# plc_esp32.net
KiCad netlist of a schematic drawn in EAGLE
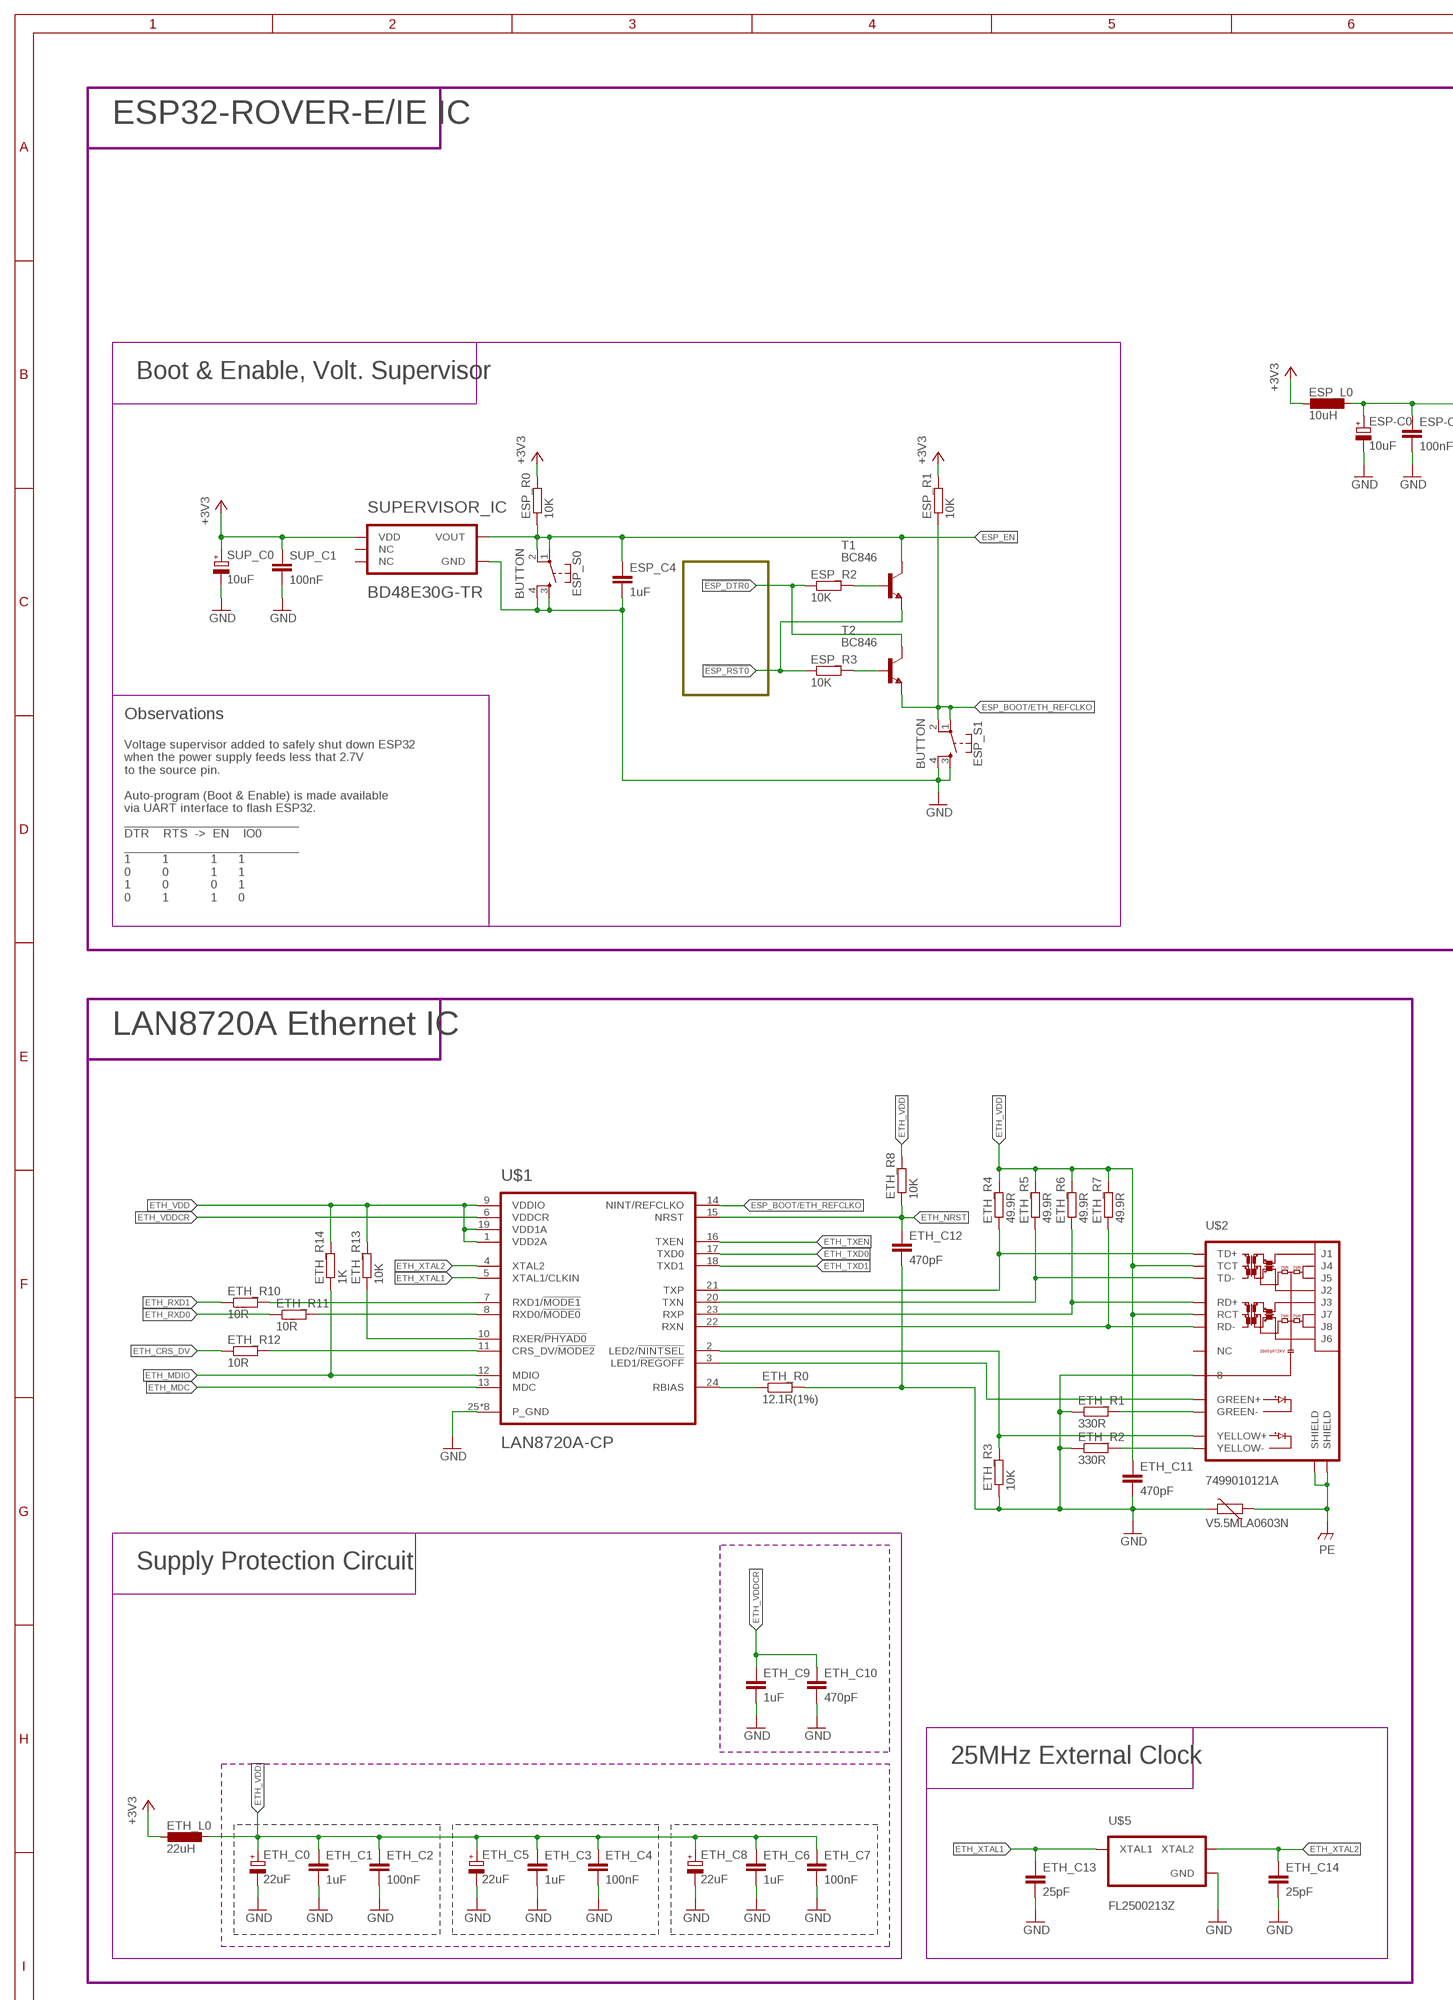
[diagram p0: schematic, sheet 1, part 1 of 2]
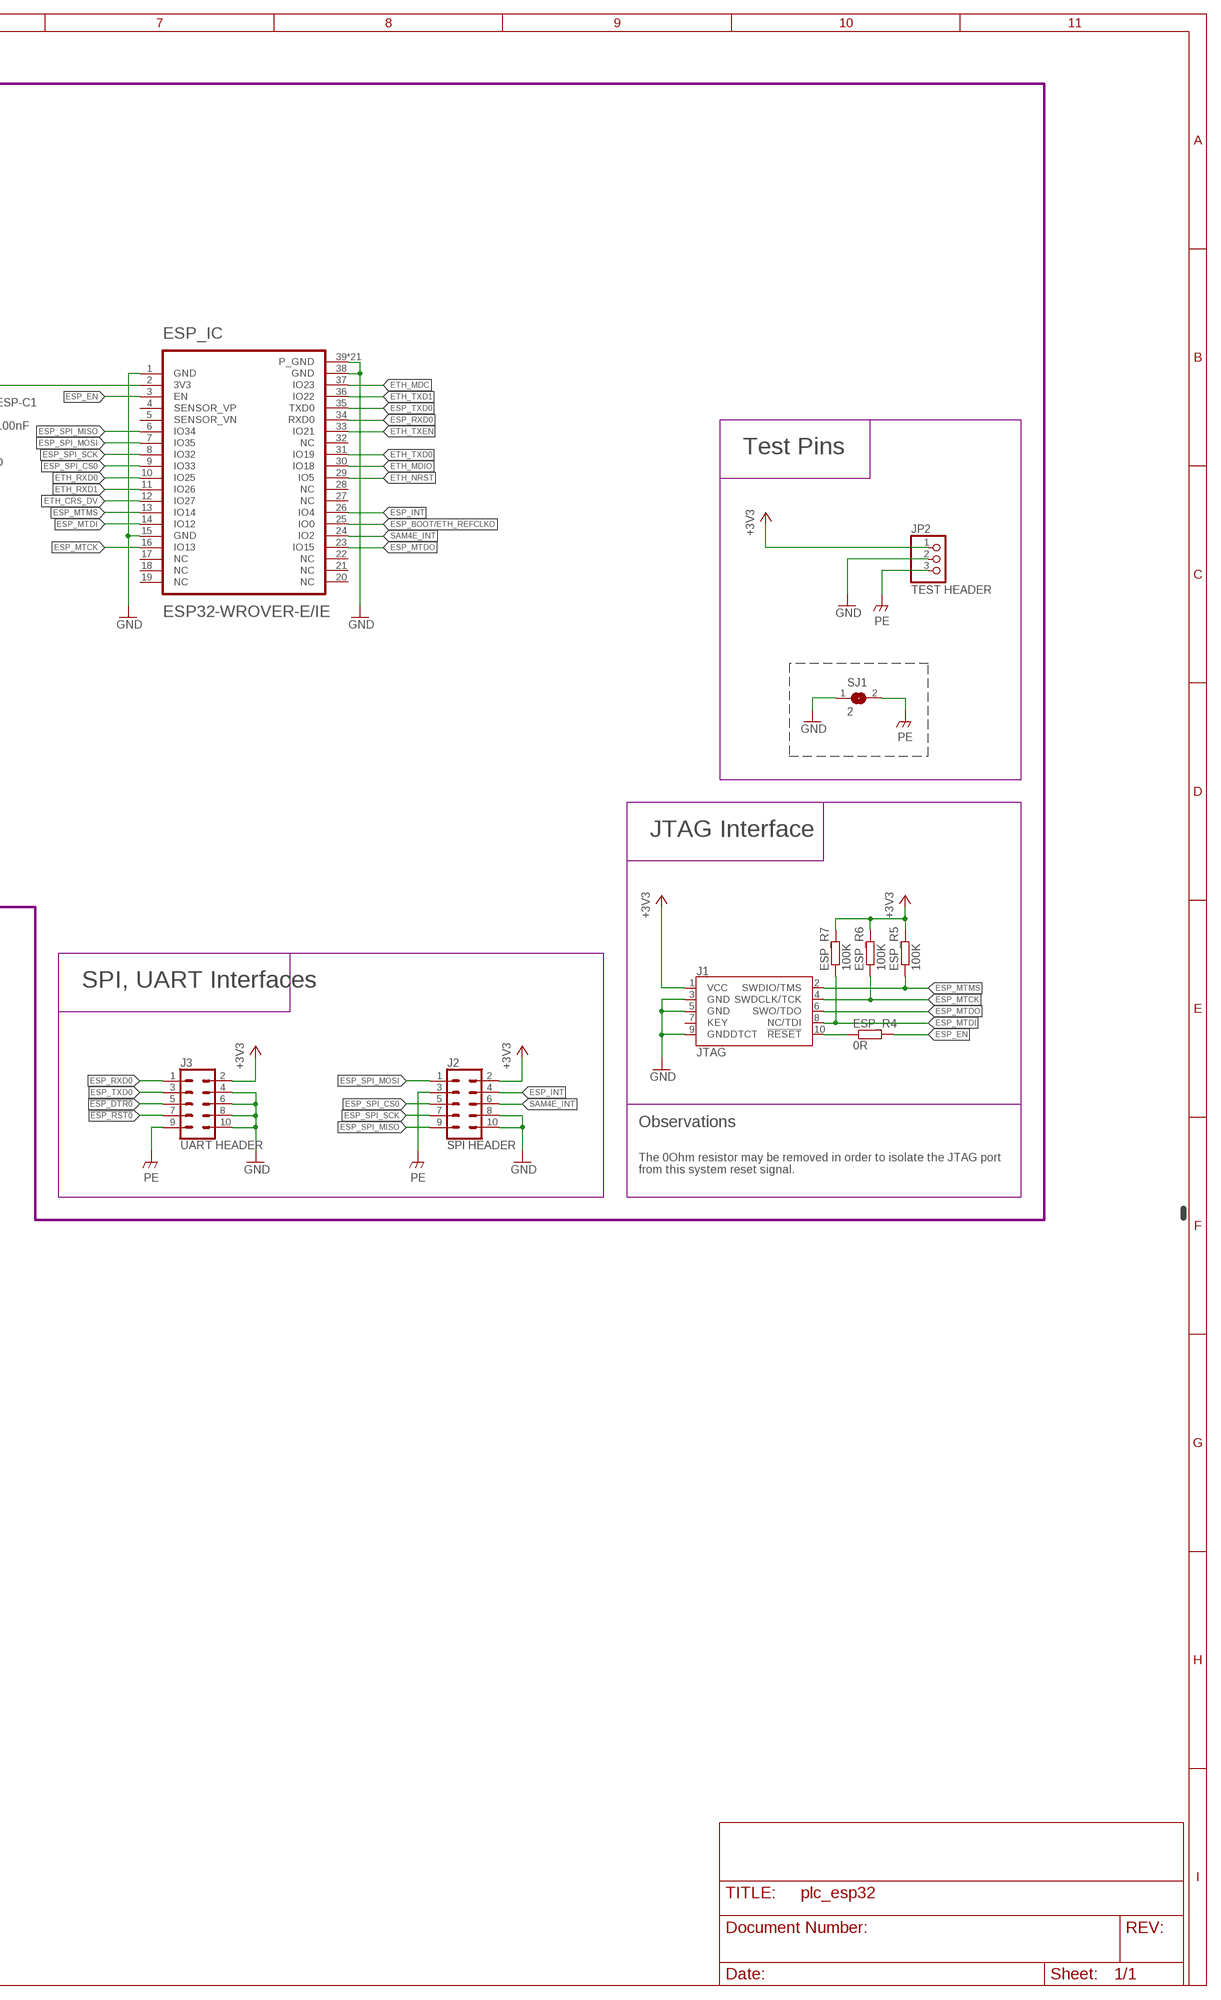
[diagram p1: schematic, sheet 1, part 2 of 2]

(export (version "E")
  (design (tool "Eeschema 10.0.6"))
  (components
    (comp (ref "ESP-C0")
      (value "10uF")
      (footprint "eagle-import:SMC_B")
      (libsource (lib "eagle-import") (part "CPOL-EUSMCB"))
    )
    (comp (ref "ESP-C1")
      (value "100nF")
      (footprint "eagle-import:C0402")
      (libsource (lib "eagle-import") (part "C-EUC0402"))
    )
    (comp (ref "ESP_C4")
      (value "1uF")
      (footprint "eagle-import:C0402")
      (libsource (lib "eagle-import") (part "C-EUC0402"))
    )
    (comp (ref "ESP_IC")
      (value "ESP32-WROVER-E/IE")
      (footprint "eagle-import:ESP32-WROVER-E_IE")
      (libsource (lib "eagle-import") (part "ESP32-WROVER-E/IE"))
    )
    (comp (ref "ESP_L0")
      (value "10uH")
      (footprint "eagle-import:L1812")
      (libsource (lib "eagle-import") (part "L-EUL1812"))
    )
    (comp (ref "ESP_R0")
      (value "10K")
      (footprint "eagle-import:R0402")
      (libsource (lib "eagle-import") (part "R-EU_R0402"))
    )
    (comp (ref "ESP_R1")
      (value "10K")
      (footprint "eagle-import:R0402")
      (libsource (lib "eagle-import") (part "R-EU_R0402"))
    )
    (comp (ref "ESP_R2")
      (value "10K")
      (footprint "eagle-import:R0402")
      (libsource (lib "eagle-import") (part "R-EU_R0402"))
    )
    (comp (ref "ESP_R3")
      (value "10K")
      (footprint "eagle-import:R0402")
      (libsource (lib "eagle-import") (part "R-EU_R0402"))
    )
    (comp (ref "ESP_R4")
      (value "0R")
      (footprint "eagle-import:R0402")
      (libsource (lib "eagle-import") (part "R-EU_R0402"))
    )
    (comp (ref "ESP_R5")
      (value "100K")
      (footprint "eagle-import:R0402")
      (libsource (lib "eagle-import") (part "R-EU_R0402"))
    )
    (comp (ref "ESP_R6")
      (value "100K")
      (footprint "eagle-import:R0402")
      (libsource (lib "eagle-import") (part "R-EU_R0402"))
    )
    (comp (ref "ESP_R7")
      (value "100K")
      (footprint "eagle-import:R0402")
      (libsource (lib "eagle-import") (part "R-EU_R0402"))
    )
    (comp (ref "ESP_S0")
      (value "BUTTON")
      (footprint "eagle-import:TACTILE_SWITCH_SMD_4.6X2.8MM")
      (libsource (lib "eagle-import") (part "MOMENTARY-SWITCH-SPST-2-SMD-4.6X2.8MM"))
    )
    (comp (ref "ESP_S1")
      (value "BUTTON")
      (footprint "eagle-import:TACTILE_SWITCH_SMD_4.6X2.8MM")
      (libsource (lib "eagle-import") (part "MOMENTARY-SWITCH-SPST-2-SMD-4.6X2.8MM"))
    )
    (comp (ref "ETH_C0")
      (value "22uF")
      (footprint "eagle-import:SMC_B")
      (libsource (lib "eagle-import") (part "CPOL-EUSMCB"))
    )
    (comp (ref "ETH_C1")
      (value "1uF")
      (footprint "eagle-import:C0402")
      (libsource (lib "eagle-import") (part "C-EUC0402"))
    )
    (comp (ref "ETH_C2")
      (value "100nF")
      (footprint "eagle-import:C0402")
      (libsource (lib "eagle-import") (part "C-EUC0402"))
    )
    (comp (ref "ETH_C3")
      (value "1uF")
      (footprint "eagle-import:C0402")
      (libsource (lib "eagle-import") (part "C-EUC0402"))
    )
    (comp (ref "ETH_C4")
      (value "100nF")
      (footprint "eagle-import:C0402")
      (libsource (lib "eagle-import") (part "C-EUC0402"))
    )
    (comp (ref "ETH_C5")
      (value "22uF")
      (footprint "eagle-import:SMC_B")
      (libsource (lib "eagle-import") (part "CPOL-EUSMCB"))
    )
    (comp (ref "ETH_C6")
      (value "1uF")
      (footprint "eagle-import:C0402")
      (libsource (lib "eagle-import") (part "C-EUC0402"))
    )
    (comp (ref "ETH_C7")
      (value "100nF")
      (footprint "eagle-import:C0402")
      (libsource (lib "eagle-import") (part "C-EUC0402"))
    )
    (comp (ref "ETH_C8")
      (value "22uF")
      (footprint "eagle-import:SMC_B")
      (libsource (lib "eagle-import") (part "CPOL-EUSMCB"))
    )
    (comp (ref "ETH_C9")
      (value "1uF")
      (footprint "eagle-import:C0402")
      (libsource (lib "eagle-import") (part "C-EUC0402"))
    )
    (comp (ref "ETH_C10")
      (value "470pF")
      (footprint "eagle-import:C0402")
      (libsource (lib "eagle-import") (part "C-EUC0402"))
    )
    (comp (ref "ETH_C11")
      (value "470pF")
      (footprint "eagle-import:C0402")
      (libsource (lib "eagle-import") (part "C-EUC0402"))
    )
    (comp (ref "ETH_C12")
      (value "470pF")
      (footprint "eagle-import:C0402")
      (libsource (lib "eagle-import") (part "C-EUC0402"))
    )
    (comp (ref "ETH_C13")
      (value "25pF")
      (footprint "eagle-import:C0402")
      (libsource (lib "eagle-import") (part "C-EUC0402"))
    )
    (comp (ref "ETH_C14")
      (value "25pF")
      (footprint "eagle-import:C0402")
      (libsource (lib "eagle-import") (part "C-EUC0402"))
    )
    (comp (ref "ETH_L0")
      (value "22uH")
      (footprint "eagle-import:L1812")
      (libsource (lib "eagle-import") (part "L-EUL1812"))
    )
    (comp (ref "ETH_R0")
      (value "12.1R(1%)")
      (footprint "eagle-import:R0402")
      (libsource (lib "eagle-import") (part "R-EU_R0402"))
    )
    (comp (ref "ETH_R1")
      (value "330R")
      (footprint "eagle-import:R0402")
      (libsource (lib "eagle-import") (part "R-EU_R0402"))
    )
    (comp (ref "ETH_R2")
      (value "330R")
      (footprint "eagle-import:R0402")
      (libsource (lib "eagle-import") (part "R-EU_R0402"))
    )
    (comp (ref "ETH_R3")
      (value "10K")
      (footprint "eagle-import:R0402")
      (libsource (lib "eagle-import") (part "R-EU_R0402"))
    )
    (comp (ref "ETH_R4")
      (value "49.9R")
      (footprint "eagle-import:R0402")
      (libsource (lib "eagle-import") (part "R-EU_R0402"))
    )
    (comp (ref "ETH_R5")
      (value "49.9R")
      (footprint "eagle-import:R0402")
      (libsource (lib "eagle-import") (part "R-EU_R0402"))
    )
    (comp (ref "ETH_R6")
      (value "49.9R")
      (footprint "eagle-import:R0402")
      (libsource (lib "eagle-import") (part "R-EU_R0402"))
    )
    (comp (ref "ETH_R7")
      (value "49.9R")
      (footprint "eagle-import:R0402")
      (libsource (lib "eagle-import") (part "R-EU_R0402"))
    )
    (comp (ref "ETH_R8")
      (value "10K")
      (footprint "eagle-import:R0402")
      (libsource (lib "eagle-import") (part "R-EU_R0402"))
    )
    (comp (ref "ETH_R10")
      (value "10R")
      (footprint "eagle-import:R0402")
      (libsource (lib "eagle-import") (part "R-EU_R0402"))
    )
    (comp (ref "ETH_R11")
      (value "10R")
      (footprint "eagle-import:R0402")
      (libsource (lib "eagle-import") (part "R-EU_R0402"))
    )
    (comp (ref "ETH_R12")
      (value "10R")
      (footprint "eagle-import:R0402")
      (libsource (lib "eagle-import") (part "R-EU_R0402"))
    )
    (comp (ref "ETH_R13")
      (value "10K")
      (footprint "eagle-import:R0402")
      (libsource (lib "eagle-import") (part "R-EU_R0402"))
    )
    (comp (ref "ETH_R14")
      (value "1K")
      (footprint "eagle-import:R0402")
      (libsource (lib "eagle-import") (part "R-EU_R0402"))
    )
    (comp (ref "J1")
      (value "JTAG")
      (footprint "eagle-import:2X5-SMD-1.27MM")
      (libsource (lib "eagle-import") (part "CORTEX_JTAG_DEBUG_SMD"))
    )
    (comp (ref "J2")
      (value "SPI HEADER")
      (footprint "eagle-import:2X5-SHROUDED_SMD")
      (libsource (lib "eagle-import") (part "CONN_05X2SHD_SMD"))
    )
    (comp (ref "J3")
      (value "UART HEADER")
      (footprint "eagle-import:2X5-SHROUDED_SMD")
      (libsource (lib "eagle-import") (part "CONN_05X2SHD_SMD"))
    )
    (comp (ref "JP2")
      (value "TEST HEADER")
      (footprint "eagle-import:1X03")
      (libsource (lib "eagle-import") (part "PINHD-1X3"))
    )
    (comp (ref "MCU_VAR1")
      (value "V5.5MLA0603N")
      (footprint "eagle-import:CT_CN0603")
      (libsource (lib "eagle-import") (part "VARISTORCN0603"))
    )
    (comp (ref "SJ1") (value "2") (footprint "eagle-import:SJ") (libsource (lib "eagle-import") (part "SJ")))
    (comp (ref "SUPERVISOR_IC")
      (value "BD48E30G-TR")
      (footprint "eagle-import:SSOP5")
      (libsource (lib "eagle-import") (part "BD48E30G-TR"))
    )
    (comp (ref "SUP_C0")
      (value "10uF")
      (footprint "eagle-import:SMC_B")
      (libsource (lib "eagle-import") (part "CPOL-EUSMCB"))
    )
    (comp (ref "SUP_C1")
      (value "100nF")
      (footprint "eagle-import:C0402")
      (libsource (lib "eagle-import") (part "C-EUC0402"))
    )
    (comp (ref "T1")
      (value "BC846")
      (footprint "eagle-import:SOT23")
      (libsource (lib "eagle-import") (part "BC846"))
    )
    (comp (ref "T2")
      (value "BC846")
      (footprint "eagle-import:SOT23")
      (libsource (lib "eagle-import") (part "BC846"))
    )
    (comp (ref "U$1")
      (value "LAN8720A-CP")
      (footprint "eagle-import:QFN-24(4X4MM)")
      (libsource (lib "eagle-import") (part "LAN8720A-CP"))
    )
    (comp (ref "U$2")
      (value "7499010121A")
      (footprint "eagle-import:RJ45-7499010121A")
      (libsource (lib "eagle-import") (part "7499010121A"))
    )
    (comp (ref "U$5")
      (value "FL2500213Z")
      (footprint "eagle-import:3.2X2.5MM")
      (libsource (lib "eagle-import") (part "FL2500213Z"))
    )
  )
  (nets
    (net (code "1") (name "+3V3") (class "Default")
      (node (ref "ESP_L0") (pin "2") (pinfunction "2_2") (pintype "passive"))
      (node (ref "ESP_R0") (pin "2") (pinfunction "2_2") (pintype "passive"))
      (node (ref "ESP_R1") (pin "2") (pinfunction "2_2") (pintype "passive"))
      (node (ref "ESP_R5") (pin "2") (pinfunction "2_2") (pintype "passive"))
      (node (ref "ESP_R6") (pin "2") (pinfunction "2_2") (pintype "passive"))
      (node (ref "ESP_R7") (pin "2") (pinfunction "2_2") (pintype "passive"))
      (node (ref "ETH_L0") (pin "2") (pinfunction "2_2") (pintype "passive"))
      (node (ref "J1") (pin "1") (pinfunction "VCC_1") (pintype "bidirectional"))
      (node (ref "J2") (pin "2") (pinfunction "2_2") (pintype "passive"))
      (node (ref "J3") (pin "2") (pinfunction "2_2") (pintype "passive"))
      (node (ref "JP2") (pin "1") (pinfunction "1_1") (pintype "passive"))
      (node (ref "SUPERVISOR_IC") (pin "2") (pinfunction "VDD_2") (pintype "bidirectional"))
      (node (ref "SUP_C0") (pin "+") (pinfunction "+_+") (pintype "passive"))
      (node (ref "SUP_C1") (pin "1") (pinfunction "1_1") (pintype "passive"))
    )
    (net (code "2") (name "/~{ESP_DTR0}") (class "Default")
      (node (ref "ESP_R2") (pin "1") (pinfunction "1_1") (pintype "passive"))
      (node (ref "J3") (pin "5") (pinfunction "5_5") (pintype "passive"))
      (node (ref "T2") (pin "3") (pinfunction "C_3") (pintype "passive"))
    )
    (net (code "3") (name "/~{ESP_RST0}") (class "Default")
      (node (ref "ESP_R3") (pin "1") (pinfunction "1_1") (pintype "passive"))
      (node (ref "J3") (pin "7") (pinfunction "7_7") (pintype "passive"))
      (node (ref "T1") (pin "2") (pinfunction "E_2") (pintype "passive"))
    )
    (net (code "4") (name "ESP_BOOT{slash}ETH_REFCLKO") (class "Default")
      (node (ref "ESP_IC") (pin "25") (pinfunction "IO0_25") (pintype "bidirectional"))
      (node (ref "ESP_R1") (pin "1") (pinfunction "1_1") (pintype "passive"))
      (node (ref "ESP_S1") (pin "1") (pinfunction "1_1") (pintype "passive"))
      (node (ref "ESP_S1") (pin "2") (pinfunction "2_2") (pintype "passive"))
      (node (ref "T2") (pin "2") (pinfunction "E_2") (pintype "passive"))
      (node (ref "U$1") (pin "14") (pinfunction "NINT/REFCLKO_14") (pintype "bidirectional"))
    )
    (net (code "5") (name "ESP_EN") (class "Default")
      (node (ref "ESP_C4") (pin "1") (pinfunction "1_1") (pintype "passive"))
      (node (ref "ESP_IC") (pin "3") (pinfunction "EN_3") (pintype "bidirectional"))
      (node (ref "ESP_R0") (pin "1") (pinfunction "1_1") (pintype "passive"))
      (node (ref "ESP_R4") (pin "2") (pinfunction "2_2") (pintype "passive"))
      (node (ref "ESP_S0") (pin "1") (pinfunction "1_1") (pintype "passive"))
      (node (ref "ESP_S0") (pin "2") (pinfunction "2_2") (pintype "passive"))
      (node (ref "SUPERVISOR_IC") (pin "1") (pinfunction "VOUT_1") (pintype "bidirectional"))
      (node (ref "T1") (pin "3") (pinfunction "C_3") (pintype "passive"))
    )
    (net (code "6") (name "ESP_INT") (class "Default")
      (node (ref "ESP_IC") (pin "26") (pinfunction "IO4_26") (pintype "bidirectional"))
      (node (ref "J2") (pin "4") (pinfunction "4_4") (pintype "passive"))
    )
    (net (code "7") (name "ESP_MTCK") (class "Default")
      (node (ref "ESP_IC") (pin "16") (pinfunction "IO13_16") (pintype "bidirectional"))
      (node (ref "ESP_R6") (pin "1") (pinfunction "1_1") (pintype "passive"))
      (node (ref "J1") (pin "4") (pinfunction "SWDCLK/TCK_4") (pintype "bidirectional"))
    )
    (net (code "8") (name "ESP_MTDI") (class "Default")
      (node (ref "ESP_IC") (pin "14") (pinfunction "IO12_14") (pintype "bidirectional"))
      (node (ref "ESP_R7") (pin "1") (pinfunction "1_1") (pintype "passive"))
      (node (ref "J1") (pin "8") (pinfunction "NC/TDI_8") (pintype "bidirectional"))
    )
    (net (code "9") (name "ESP_MTDO") (class "Default")
      (node (ref "ESP_IC") (pin "23") (pinfunction "IO15_23") (pintype "bidirectional"))
      (node (ref "J1") (pin "6") (pinfunction "SWO/TDO_6") (pintype "bidirectional"))
    )
    (net (code "10") (name "ESP_MTMS") (class "Default")
      (node (ref "ESP_IC") (pin "13") (pinfunction "IO14_13") (pintype "bidirectional"))
      (node (ref "ESP_R5") (pin "1") (pinfunction "1_1") (pintype "passive"))
      (node (ref "J1") (pin "2") (pinfunction "SWDIO/TMS_2") (pintype "bidirectional"))
    )
    (net (code "11") (name "ESP_RXD0") (class "Default")
      (node (ref "ESP_IC") (pin "34") (pinfunction "RXD0_34") (pintype "bidirectional"))
      (node (ref "J3") (pin "1") (pinfunction "1_1") (pintype "passive"))
    )
    (net (code "12") (name "ESP_SPI_CS0") (class "Default")
      (node (ref "ESP_IC") (pin "9") (pinfunction "IO33_9") (pintype "bidirectional"))
      (node (ref "J2") (pin "5") (pinfunction "5_5") (pintype "passive"))
    )
    (net (code "13") (name "ESP_SPI_MISO") (class "Default")
      (node (ref "ESP_IC") (pin "6") (pinfunction "IO34_6") (pintype "bidirectional"))
      (node (ref "J2") (pin "9") (pinfunction "9_9") (pintype "passive"))
    )
    (net (code "14") (name "ESP_SPI_MOSI") (class "Default")
      (node (ref "ESP_IC") (pin "7") (pinfunction "IO35_7") (pintype "bidirectional"))
      (node (ref "J2") (pin "1") (pinfunction "1_1") (pintype "passive"))
    )
    (net (code "15") (name "ESP_SPI_SCK") (class "Default")
      (node (ref "ESP_IC") (pin "8") (pinfunction "IO32_8") (pintype "bidirectional"))
      (node (ref "J2") (pin "7") (pinfunction "7_7") (pintype "passive"))
    )
    (net (code "16") (name "ESP_TXD0") (class "Default")
      (node (ref "ESP_IC") (pin "35") (pinfunction "TXD0_35") (pintype "bidirectional"))
      (node (ref "J3") (pin "3") (pinfunction "3_3") (pintype "passive"))
    )
    (net (code "17") (name "ETH_CRS_DV") (class "Default")
      (node (ref "ESP_IC") (pin "12") (pinfunction "IO27_12") (pintype "bidirectional"))
      (node (ref "ETH_R12") (pin "1") (pinfunction "1_1") (pintype "passive"))
    )
    (net (code "18") (name "ETH_MDC") (class "Default")
      (node (ref "ESP_IC") (pin "37") (pinfunction "IO23_37") (pintype "bidirectional"))
      (node (ref "U$1") (pin "13") (pinfunction "MDC_13") (pintype "bidirectional"))
    )
    (net (code "19") (name "ETH_MDIO") (class "Default")
      (node (ref "ESP_IC") (pin "30") (pinfunction "IO18_30") (pintype "bidirectional"))
      (node (ref "ETH_R14") (pin "1") (pinfunction "1_1") (pintype "passive"))
      (node (ref "U$1") (pin "12") (pinfunction "MDIO_12") (pintype "bidirectional"))
    )
    (net (code "20") (name "ETH_NRST") (class "Default")
      (node (ref "ESP_IC") (pin "29") (pinfunction "IO5_29") (pintype "bidirectional"))
      (node (ref "ETH_C12") (pin "1") (pinfunction "1_1") (pintype "passive"))
      (node (ref "ETH_R8") (pin "1") (pinfunction "1_1") (pintype "passive"))
      (node (ref "U$1") (pin "15") (pinfunction "NRST_15") (pintype "bidirectional"))
    )
    (net (code "21") (name "ETH_RXD0") (class "Default")
      (node (ref "ESP_IC") (pin "10") (pinfunction "IO25_10") (pintype "bidirectional"))
      (node (ref "ETH_R11") (pin "1") (pinfunction "1_1") (pintype "passive"))
    )
    (net (code "22") (name "ETH_RXD1") (class "Default")
      (node (ref "ESP_IC") (pin "11") (pinfunction "IO26_11") (pintype "bidirectional"))
      (node (ref "ETH_R10") (pin "1") (pinfunction "1_1") (pintype "passive"))
    )
    (net (code "23") (name "ETH_TXD0") (class "Default")
      (node (ref "ESP_IC") (pin "31") (pinfunction "IO19_31") (pintype "bidirectional"))
      (node (ref "U$1") (pin "17") (pinfunction "TXD0_17") (pintype "bidirectional"))
    )
    (net (code "24") (name "ETH_TXD1") (class "Default")
      (node (ref "ESP_IC") (pin "36") (pinfunction "IO22_36") (pintype "bidirectional"))
      (node (ref "U$1") (pin "18") (pinfunction "TXD1_18") (pintype "bidirectional"))
    )
    (net (code "25") (name "ETH_TXEN") (class "Default")
      (node (ref "ESP_IC") (pin "33") (pinfunction "IO21_33") (pintype "bidirectional"))
      (node (ref "U$1") (pin "16") (pinfunction "TXEN_16") (pintype "bidirectional"))
    )
    (net (code "26") (name "ETH_VDD") (class "Default")
      (node (ref "ETH_C0") (pin "+") (pinfunction "+_+") (pintype "passive"))
      (node (ref "ETH_C1") (pin "1") (pinfunction "1_1") (pintype "passive"))
      (node (ref "ETH_C11") (pin "1") (pinfunction "1_1") (pintype "passive"))
      (node (ref "ETH_C2") (pin "1") (pinfunction "1_1") (pintype "passive"))
      (node (ref "ETH_C3") (pin "1") (pinfunction "1_1") (pintype "passive"))
      (node (ref "ETH_C4") (pin "1") (pinfunction "1_1") (pintype "passive"))
      (node (ref "ETH_C5") (pin "+") (pinfunction "+_+") (pintype "passive"))
      (node (ref "ETH_C6") (pin "1") (pinfunction "1_1") (pintype "passive"))
      (node (ref "ETH_C7") (pin "1") (pinfunction "1_1") (pintype "passive"))
      (node (ref "ETH_C8") (pin "+") (pinfunction "+_+") (pintype "passive"))
      (node (ref "ETH_L0") (pin "1") (pinfunction "1_1") (pintype "passive"))
      (node (ref "ETH_R13") (pin "2") (pinfunction "2_2") (pintype "passive"))
      (node (ref "ETH_R14") (pin "2") (pinfunction "2_2") (pintype "passive"))
      (node (ref "ETH_R4") (pin "2") (pinfunction "2_2") (pintype "passive"))
      (node (ref "ETH_R5") (pin "2") (pinfunction "2_2") (pintype "passive"))
      (node (ref "ETH_R6") (pin "2") (pinfunction "2_2") (pintype "passive"))
      (node (ref "ETH_R7") (pin "2") (pinfunction "2_2") (pintype "passive"))
      (node (ref "ETH_R8") (pin "2") (pinfunction "2_2") (pintype "passive"))
      (node (ref "U$1") (pin "1") (pinfunction "VDD2A_1") (pintype "bidirectional"))
      (node (ref "U$1") (pin "19") (pinfunction "VDD1A_19") (pintype "bidirectional"))
      (node (ref "U$1") (pin "9") (pinfunction "VDDIO_9") (pintype "bidirectional"))
      (node (ref "U$2") (pin "2") (pinfunction "TCT_2") (pintype "bidirectional"))
      (node (ref "U$2") (pin "5") (pinfunction "RCT_5") (pintype "bidirectional"))
    )
    (net (code "27") (name "ETH_VDDCR") (class "Default")
      (node (ref "ETH_C10") (pin "1") (pinfunction "1_1") (pintype "passive"))
      (node (ref "ETH_C9") (pin "1") (pinfunction "1_1") (pintype "passive"))
      (node (ref "U$1") (pin "6") (pinfunction "VDDCR_6") (pintype "bidirectional"))
    )
    (net (code "28") (name "ETH_XTAL1") (class "Default")
      (node (ref "ETH_C13") (pin "1") (pinfunction "1_1") (pintype "passive"))
      (node (ref "U$1") (pin "5") (pinfunction "XTAL1/CLKIN_5") (pintype "bidirectional"))
      (node (ref "U$5") (pin "1") (pinfunction "XTAL1_1") (pintype "bidirectional"))
    )
    (net (code "29") (name "ETH_XTAL2") (class "Default")
      (node (ref "ETH_C14") (pin "1") (pinfunction "1_1") (pintype "passive"))
      (node (ref "U$1") (pin "4") (pinfunction "XTAL2_4") (pintype "bidirectional"))
      (node (ref "U$5") (pin "3") (pinfunction "XTAL2_3") (pintype "bidirectional"))
    )
    (net (code "30") (name "GND") (class "Default")
      (node (ref "ESP-C0") (pin "-") (pinfunction "-_-") (pintype "passive"))
      (node (ref "ESP-C1") (pin "2") (pinfunction "2_2") (pintype "passive"))
      (node (ref "ESP_C4") (pin "2") (pinfunction "2_2") (pintype "passive"))
      (node (ref "ESP_IC") (pin "1") (pinfunction "GND_1") (pintype "bidirectional"))
      (node (ref "ESP_IC") (pin "15") (pinfunction "GND_15") (pintype "bidirectional"))
      (node (ref "ESP_IC") (pin "38") (pinfunction "GND_38") (pintype "bidirectional"))
      (node (ref "ESP_IC") (pin "39") (pinfunction "P_GND_39") (pintype "bidirectional"))
      (node (ref "ESP_IC") (pin "40") (pinfunction "P_GND_40") (pintype "bidirectional"))
      (node (ref "ESP_IC") (pin "41") (pinfunction "P_GND_41") (pintype "bidirectional"))
      (node (ref "ESP_IC") (pin "42") (pinfunction "P_GND_42") (pintype "bidirectional"))
      (node (ref "ESP_IC") (pin "43") (pinfunction "P_GND_43") (pintype "bidirectional"))
      (node (ref "ESP_IC") (pin "44") (pinfunction "P_GND_44") (pintype "bidirectional"))
      (node (ref "ESP_IC") (pin "45") (pinfunction "P_GND_45") (pintype "bidirectional"))
      (node (ref "ESP_IC") (pin "46") (pinfunction "P_GND_46") (pintype "bidirectional"))
      (node (ref "ESP_IC") (pin "47") (pinfunction "P_GND_47") (pintype "bidirectional"))
      (node (ref "ESP_IC") (pin "48") (pinfunction "P_GND_48") (pintype "bidirectional"))
      (node (ref "ESP_IC") (pin "49") (pinfunction "P_GND_49") (pintype "bidirectional"))
      (node (ref "ESP_IC") (pin "50") (pinfunction "P_GND_50") (pintype "bidirectional"))
      (node (ref "ESP_IC") (pin "51") (pinfunction "P_GND_51") (pintype "bidirectional"))
      (node (ref "ESP_IC") (pin "52") (pinfunction "P_GND_52") (pintype "bidirectional"))
      (node (ref "ESP_IC") (pin "53") (pinfunction "P_GND_53") (pintype "bidirectional"))
      (node (ref "ESP_IC") (pin "54") (pinfunction "P_GND_54") (pintype "bidirectional"))
      (node (ref "ESP_IC") (pin "55") (pinfunction "P_GND_55") (pintype "bidirectional"))
      (node (ref "ESP_IC") (pin "56") (pinfunction "P_GND_56") (pintype "bidirectional"))
      (node (ref "ESP_IC") (pin "57") (pinfunction "P_GND_57") (pintype "bidirectional"))
      (node (ref "ESP_IC") (pin "58") (pinfunction "P_GND_58") (pintype "bidirectional"))
      (node (ref "ESP_IC") (pin "59") (pinfunction "P_GND_59") (pintype "bidirectional"))
      (node (ref "ESP_S0") (pin "3") (pinfunction "3_3") (pintype "passive"))
      (node (ref "ESP_S0") (pin "4") (pinfunction "4_4") (pintype "passive"))
      (node (ref "ESP_S1") (pin "3") (pinfunction "3_3") (pintype "passive"))
      (node (ref "ESP_S1") (pin "4") (pinfunction "4_4") (pintype "passive"))
      (node (ref "ETH_C0") (pin "-") (pinfunction "-_-") (pintype "passive"))
      (node (ref "ETH_C1") (pin "2") (pinfunction "2_2") (pintype "passive"))
      (node (ref "ETH_C10") (pin "2") (pinfunction "2_2") (pintype "passive"))
      (node (ref "ETH_C11") (pin "2") (pinfunction "2_2") (pintype "passive"))
      (node (ref "ETH_C12") (pin "2") (pinfunction "2_2") (pintype "passive"))
      (node (ref "ETH_C13") (pin "2") (pinfunction "2_2") (pintype "passive"))
      (node (ref "ETH_C14") (pin "2") (pinfunction "2_2") (pintype "passive"))
      (node (ref "ETH_C2") (pin "2") (pinfunction "2_2") (pintype "passive"))
      (node (ref "ETH_C3") (pin "2") (pinfunction "2_2") (pintype "passive"))
      (node (ref "ETH_C4") (pin "2") (pinfunction "2_2") (pintype "passive"))
      (node (ref "ETH_C5") (pin "-") (pinfunction "-_-") (pintype "passive"))
      (node (ref "ETH_C6") (pin "2") (pinfunction "2_2") (pintype "passive"))
      (node (ref "ETH_C7") (pin "2") (pinfunction "2_2") (pintype "passive"))
      (node (ref "ETH_C8") (pin "-") (pinfunction "-_-") (pintype "passive"))
      (node (ref "ETH_C9") (pin "2") (pinfunction "2_2") (pintype "passive"))
      (node (ref "ETH_R0") (pin "2") (pinfunction "2_2") (pintype "passive"))
      (node (ref "ETH_R1") (pin "1") (pinfunction "1_1") (pintype "passive"))
      (node (ref "ETH_R2") (pin "1") (pinfunction "1_1") (pintype "passive"))
      (node (ref "ETH_R3") (pin "1") (pinfunction "1_1") (pintype "passive"))
      (node (ref "J1") (pin "3") (pinfunction "GND_3") (pintype "bidirectional"))
      (node (ref "J1") (pin "5") (pinfunction "GND_5") (pintype "bidirectional"))
      (node (ref "J1") (pin "9") (pinfunction "GNDDTCT_9") (pintype "bidirectional"))
      (node (ref "J2") (pin "10") (pinfunction "10_10") (pintype "passive"))
      (node (ref "J2") (pin "8") (pinfunction "8_8") (pintype "passive"))
      (node (ref "J3") (pin "10") (pinfunction "10_10") (pintype "passive"))
      (node (ref "J3") (pin "4") (pinfunction "4_4") (pintype "passive"))
      (node (ref "J3") (pin "6") (pinfunction "6_6") (pintype "passive"))
      (node (ref "J3") (pin "8") (pinfunction "8_8") (pintype "passive"))
      (node (ref "JP2") (pin "2") (pinfunction "2_2") (pintype "passive"))
      (node (ref "MCU_VAR1") (pin "2") (pinfunction "2_2") (pintype "passive"))
      (node (ref "SJ1") (pin "1") (pinfunction "1_1") (pintype "passive"))
      (node (ref "SUPERVISOR_IC") (pin "3") (pinfunction "GND_3") (pintype "bidirectional"))
      (node (ref "SUP_C0") (pin "-") (pinfunction "-_-") (pintype "passive"))
      (node (ref "SUP_C1") (pin "2") (pinfunction "2_2") (pintype "passive"))
      (node (ref "U$1") (pin "25") (pinfunction "P_GND_25") (pintype "bidirectional"))
      (node (ref "U$1") (pin "26") (pinfunction "P_GND_26") (pintype "bidirectional"))
      (node (ref "U$1") (pin "27") (pinfunction "P_GND_27") (pintype "bidirectional"))
      (node (ref "U$1") (pin "28") (pinfunction "P_GND_28") (pintype "bidirectional"))
      (node (ref "U$1") (pin "29") (pinfunction "P_GND_29") (pintype "bidirectional"))
      (node (ref "U$1") (pin "30") (pinfunction "P_GND_30") (pintype "bidirectional"))
      (node (ref "U$1") (pin "31") (pinfunction "P_GND_31") (pintype "bidirectional"))
      (node (ref "U$1") (pin "32") (pinfunction "P_GND_32") (pintype "bidirectional"))
      (node (ref "U$2") (pin "8") (pinfunction "8_8") (pintype "bidirectional"))
      (node (ref "U$5") (pin "2") (pinfunction "GND_2") (pintype "bidirectional"))
      (node (ref "U$5") (pin "4") (pinfunction "GND_4") (pintype "bidirectional"))
    )
    (net (code "31") (name "Net-(ESP_IC-3V3)") (class "Default")
      (node (ref "ESP-C0") (pin "+") (pinfunction "+_+") (pintype "passive"))
      (node (ref "ESP-C1") (pin "1") (pinfunction "1_1") (pintype "passive"))
      (node (ref "ESP_IC") (pin "2") (pinfunction "3V3_2") (pintype "bidirectional"))
      (node (ref "ESP_L0") (pin "1") (pinfunction "1_1") (pintype "passive"))
    )
    (net (code "32") (name "Net-(J1-~{RESET})") (class "Default")
      (node (ref "ESP_R4") (pin "1") (pinfunction "1_1") (pintype "passive"))
      (node (ref "J1") (pin "10") (pinfunction "~{RESET}_10") (pintype "bidirectional"))
    )
    (net (code "33") (name "Net-(T1-B)") (class "Default")
      (node (ref "ESP_R2") (pin "2") (pinfunction "2_2") (pintype "passive"))
      (node (ref "T1") (pin "1") (pinfunction "B_1") (pintype "passive"))
    )
    (net (code "34") (name "Net-(T2-B)") (class "Default")
      (node (ref "ESP_R3") (pin "2") (pinfunction "2_2") (pintype "passive"))
      (node (ref "T2") (pin "1") (pinfunction "B_1") (pintype "passive"))
    )
    (net (code "35") (name "Net-(U$1-CRS_DV{slash}~{MODE2})") (class "Default")
      (node (ref "ETH_R12") (pin "2") (pinfunction "2_2") (pintype "passive"))
      (node (ref "U$1") (pin "11") (pinfunction "CRS_DV/~{MODE2}_11") (pintype "bidirectional"))
    )
    (net (code "36") (name "Net-(U$1-LED1{slash}~{REGOFF})") (class "Default")
      (node (ref "U$1") (pin "3") (pinfunction "LED1/~{REGOFF}_3") (pintype "bidirectional"))
      (node (ref "U$2") (pin "10") (pinfunction "GREEN+_10") (pintype "bidirectional"))
    )
    (net (code "37") (name "Net-(U$1-LED2{slash}~{NINTSEL})") (class "Default")
      (node (ref "ETH_R3") (pin "2") (pinfunction "2_2") (pintype "passive"))
      (node (ref "U$1") (pin "2") (pinfunction "LED2/~{NINTSEL}_2") (pintype "bidirectional"))
      (node (ref "U$2") (pin "12") (pinfunction "YELLOW+_12") (pintype "bidirectional"))
    )
    (net (code "38") (name "Net-(U$1-RBIAS)") (class "Default")
      (node (ref "ETH_R0") (pin "1") (pinfunction "1_1") (pintype "passive"))
      (node (ref "U$1") (pin "24") (pinfunction "RBIAS_24") (pintype "bidirectional"))
    )
    (net (code "39") (name "Net-(U$1-RXD0{slash}~{MODE0})") (class "Default")
      (node (ref "ETH_R11") (pin "2") (pinfunction "2_2") (pintype "passive"))
      (node (ref "U$1") (pin "8") (pinfunction "RXD0/~{MODE0}_8") (pintype "bidirectional"))
    )
    (net (code "40") (name "Net-(U$1-RXD1{slash}~{MODE1})") (class "Default")
      (node (ref "ETH_R10") (pin "2") (pinfunction "2_2") (pintype "passive"))
      (node (ref "U$1") (pin "7") (pinfunction "RXD1/~{MODE1}_7") (pintype "bidirectional"))
    )
    (net (code "41") (name "Net-(U$1-RXER{slash}~{PHYAD0})") (class "Default")
      (node (ref "ETH_R13") (pin "1") (pinfunction "1_1") (pintype "passive"))
      (node (ref "U$1") (pin "10") (pinfunction "RXER/~{PHYAD0}_10") (pintype "bidirectional"))
    )
    (net (code "42") (name "Net-(U$1-RXN)") (class "Default")
      (node (ref "ETH_R7") (pin "1") (pinfunction "1_1") (pintype "passive"))
      (node (ref "U$1") (pin "22") (pinfunction "RXN_22") (pintype "bidirectional"))
      (node (ref "U$2") (pin "6") (pinfunction "RD-_6") (pintype "bidirectional"))
    )
    (net (code "43") (name "Net-(U$1-RXP)") (class "Default")
      (node (ref "ETH_R6") (pin "1") (pinfunction "1_1") (pintype "passive"))
      (node (ref "U$1") (pin "23") (pinfunction "RXP_23") (pintype "bidirectional"))
      (node (ref "U$2") (pin "4") (pinfunction "RD+_4") (pintype "bidirectional"))
    )
    (net (code "44") (name "Net-(U$1-TXN)") (class "Default")
      (node (ref "ETH_R5") (pin "1") (pinfunction "1_1") (pintype "passive"))
      (node (ref "U$1") (pin "20") (pinfunction "TXN_20") (pintype "bidirectional"))
      (node (ref "U$2") (pin "3") (pinfunction "TD-_3") (pintype "bidirectional"))
    )
    (net (code "45") (name "Net-(U$1-TXP)") (class "Default")
      (node (ref "ETH_R4") (pin "1") (pinfunction "1_1") (pintype "passive"))
      (node (ref "U$1") (pin "21") (pinfunction "TXP_21") (pintype "bidirectional"))
      (node (ref "U$2") (pin "1") (pinfunction "TD+_1") (pintype "bidirectional"))
    )
    (net (code "46") (name "Net-(U$2-GREEN-)") (class "Default")
      (node (ref "ETH_R1") (pin "2") (pinfunction "2_2") (pintype "passive"))
      (node (ref "U$2") (pin "9") (pinfunction "GREEN-_9") (pintype "bidirectional"))
    )
    (net (code "47") (name "Net-(U$2-YELLOW-)") (class "Default")
      (node (ref "ETH_R2") (pin "2") (pinfunction "2_2") (pintype "passive"))
      (node (ref "U$2") (pin "11") (pinfunction "YELLOW-_11") (pintype "bidirectional"))
    )
    (net (code "48") (name "PE") (class "Default")
      (node (ref "J2") (pin "3") (pinfunction "3_3") (pintype "passive"))
      (node (ref "J3") (pin "9") (pinfunction "9_9") (pintype "passive"))
      (node (ref "JP2") (pin "3") (pinfunction "3_3") (pintype "passive"))
      (node (ref "MCU_VAR1") (pin "1") (pinfunction "1_1") (pintype "passive"))
      (node (ref "SJ1") (pin "2") (pinfunction "2_2") (pintype "passive"))
      (node (ref "U$2") (pin "13") (pinfunction "SHIELD_13") (pintype "bidirectional"))
      (node (ref "U$2") (pin "14") (pinfunction "SHIELD_14") (pintype "bidirectional"))
    )
    (net (code "49") (name "SAM4E_INT") (class "Default")
      (node (ref "ESP_IC") (pin "24") (pinfunction "IO2_24") (pintype "bidirectional"))
      (node (ref "J2") (pin "6") (pinfunction "6_6") (pintype "passive"))
    )
    (net (code "50") (name "unconnected-(ESP_IC-NC-Pad17)") (class "Default")
      (node (ref "ESP_IC") (pin "17") (pinfunction "NC_17") (pintype "bidirectional"))
    )
    (net (code "51") (name "unconnected-(ESP_IC-NC-Pad18)") (class "Default")
      (node (ref "ESP_IC") (pin "18") (pinfunction "NC_18") (pintype "bidirectional"))
    )
    (net (code "52") (name "unconnected-(ESP_IC-NC-Pad19)") (class "Default")
      (node (ref "ESP_IC") (pin "19") (pinfunction "NC_19") (pintype "bidirectional"))
    )
    (net (code "53") (name "unconnected-(ESP_IC-NC-Pad20)") (class "Default")
      (node (ref "ESP_IC") (pin "20") (pinfunction "NC_20") (pintype "bidirectional"))
    )
    (net (code "54") (name "unconnected-(ESP_IC-NC-Pad21)") (class "Default")
      (node (ref "ESP_IC") (pin "21") (pinfunction "NC_21") (pintype "bidirectional"))
    )
    (net (code "55") (name "unconnected-(ESP_IC-NC-Pad22)") (class "Default")
      (node (ref "ESP_IC") (pin "22") (pinfunction "NC_22") (pintype "bidirectional"))
    )
    (net (code "56") (name "unconnected-(ESP_IC-NC-Pad27)") (class "Default")
      (node (ref "ESP_IC") (pin "27") (pinfunction "NC_27") (pintype "bidirectional"))
    )
    (net (code "57") (name "unconnected-(ESP_IC-NC-Pad28)") (class "Default")
      (node (ref "ESP_IC") (pin "28") (pinfunction "NC_28") (pintype "bidirectional"))
    )
    (net (code "58") (name "unconnected-(ESP_IC-NC-Pad32)") (class "Default")
      (node (ref "ESP_IC") (pin "32") (pinfunction "NC_32") (pintype "bidirectional"))
    )
    (net (code "59") (name "unconnected-(ESP_IC-SENSOR_VN-Pad5)") (class "Default")
      (node (ref "ESP_IC") (pin "5") (pinfunction "SENSOR_VN_5") (pintype "bidirectional"))
    )
    (net (code "60") (name "unconnected-(ESP_IC-SENSOR_VP-Pad4)") (class "Default")
      (node (ref "ESP_IC") (pin "4") (pinfunction "SENSOR_VP_4") (pintype "bidirectional"))
    )
    (net (code "61") (name "unconnected-(J1-KEY-Pad7)") (class "Default")
      (node (ref "J1") (pin "7") (pinfunction "KEY_7") (pintype "bidirectional"))
    )
    (net (code "62") (name "unconnected-(SUPERVISOR_IC-NC-Pad4)") (class "Default")
      (node (ref "SUPERVISOR_IC") (pin "4") (pinfunction "NC_4") (pintype "bidirectional"))
    )
    (net (code "63") (name "unconnected-(SUPERVISOR_IC-NC-Pad5)") (class "Default")
      (node (ref "SUPERVISOR_IC") (pin "5") (pinfunction "NC_5") (pintype "bidirectional"))
    )
    (net (code "64") (name "unconnected-(U$2-NC-Pad7)") (class "Default")
      (node (ref "U$2") (pin "7") (pinfunction "NC_7") (pintype "bidirectional"))
    )
  )
)
